# S_NES2USB.net
KiCad netlist of a schematic drawn in EAGLE
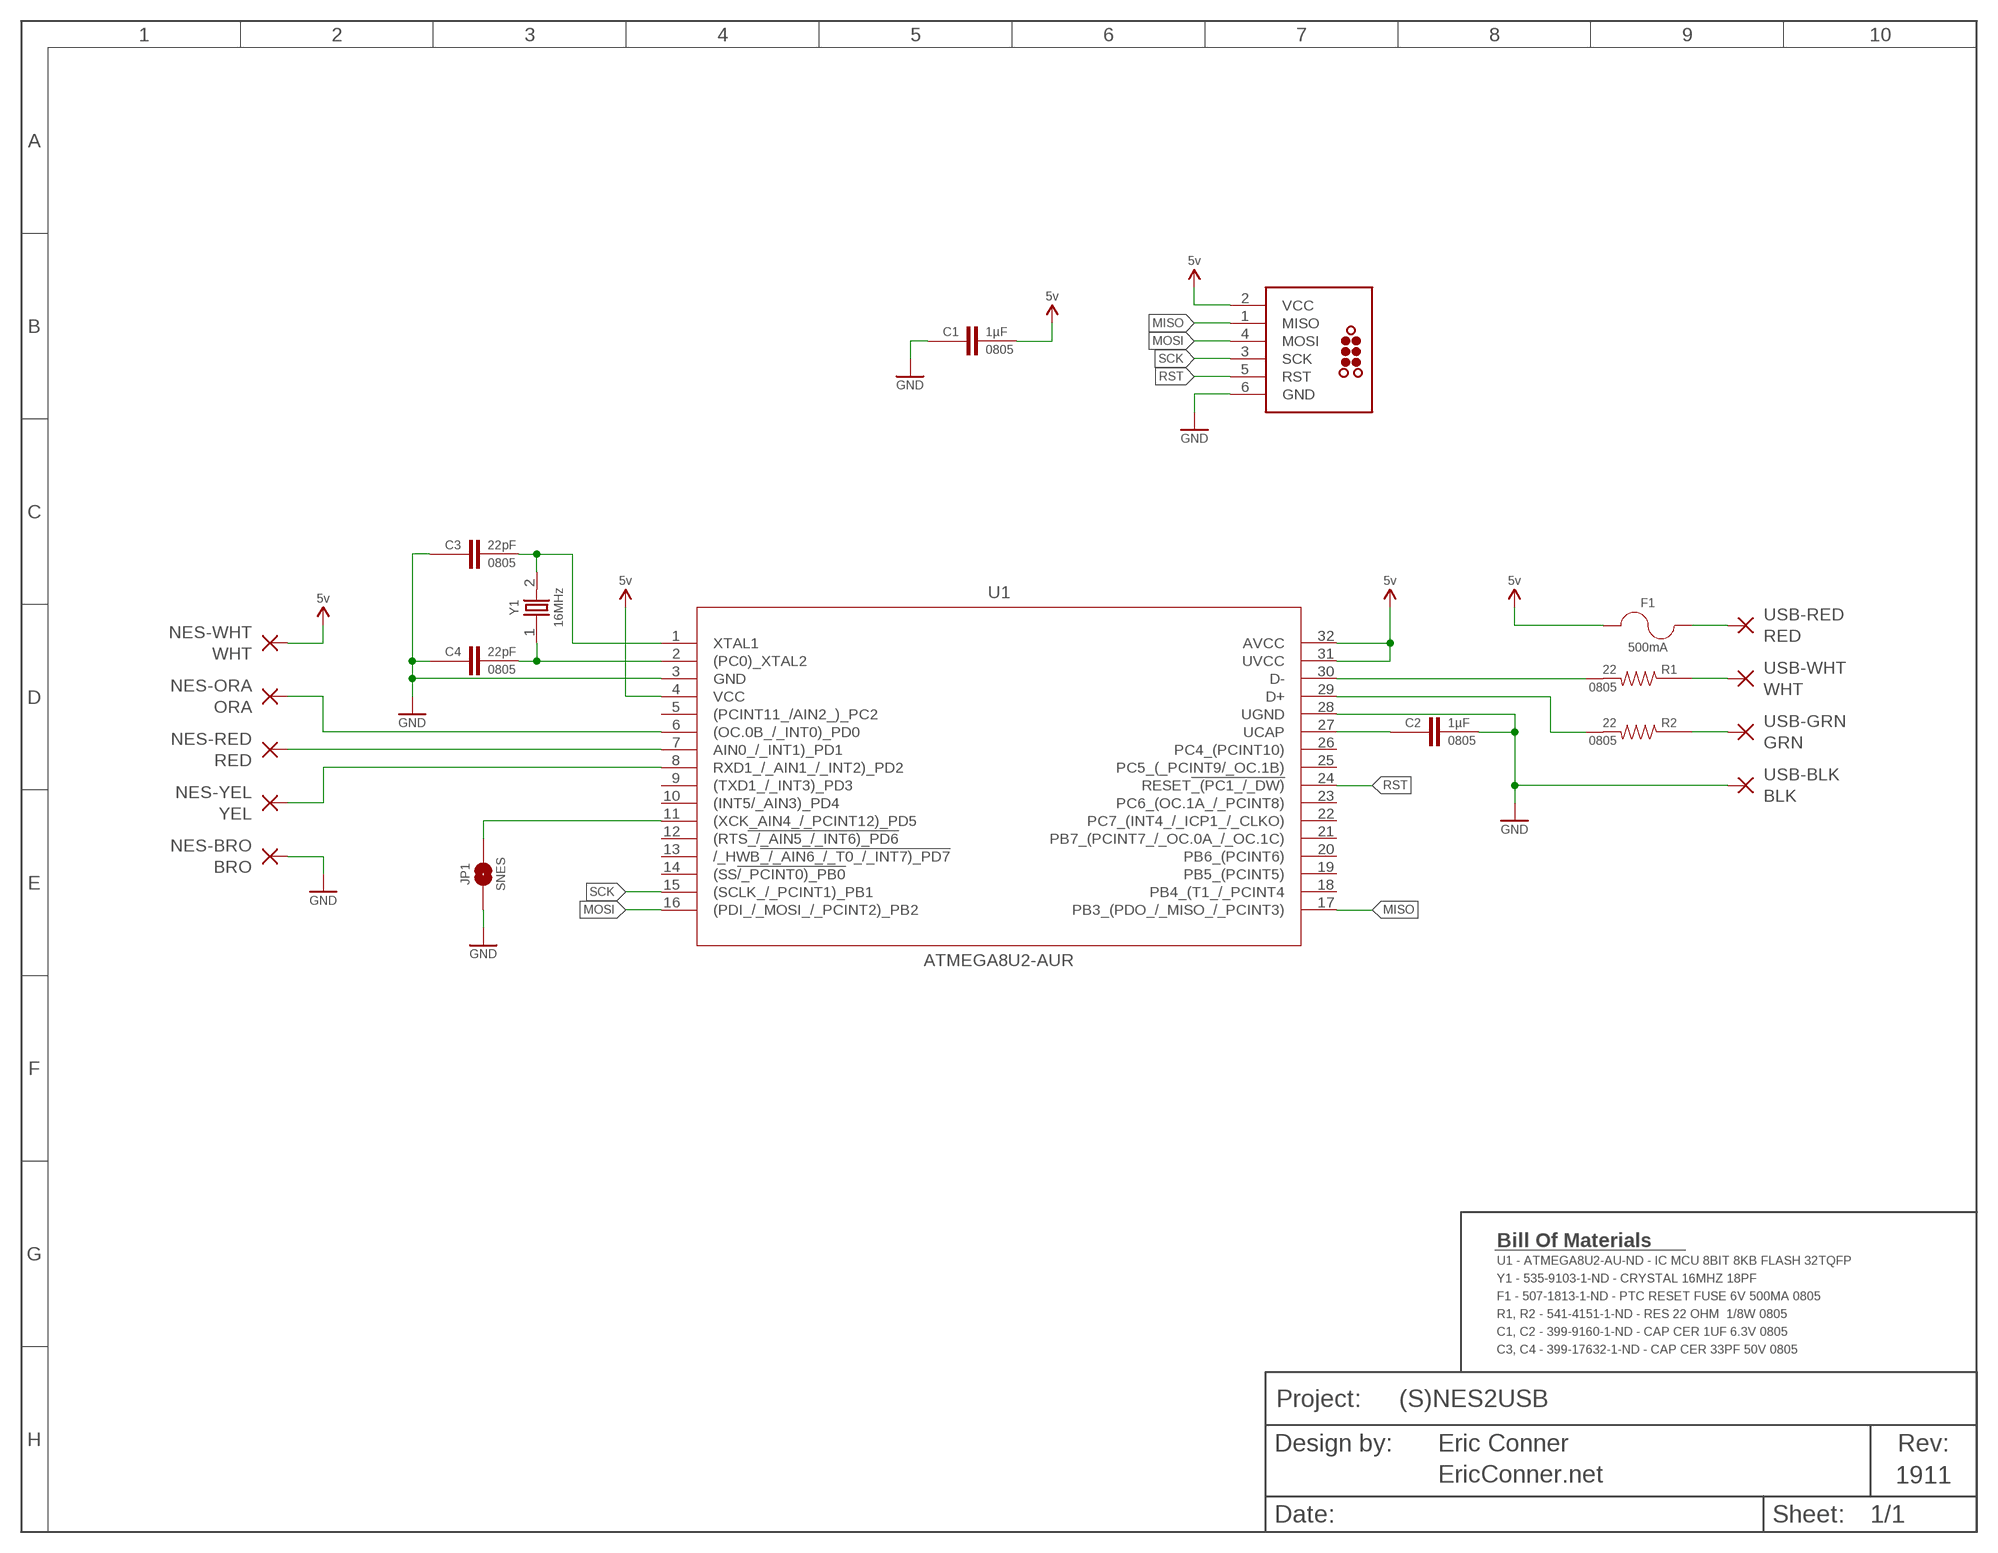
[diagram p0: schematic, sheet 1]

(export (version "E")
  (design (tool "Eeschema 10.0.6"))
  (components
    (comp (ref "BORDER1")
      (value "BORDER_LETTER-MINIMAL")
      (footprint "eagle-import:MINIMAL_LOGO")
      (fields
        (field (name "DESIGNER") "Eric Conner")
        (field (name "PROJECT") "(S)NES2USB")
        (field (name "VERSION") "1911")
        (field (name "WEBSITE") "EricConner.net")
        (field (name "DESIGNER_1") "Eric Conner")
        (field (name "PROJECT_1") "(S)NES2USB")
        (field (name "VERSION_1") "1911")
        (field (name "WEBSITE_1") "EricConner.net")
      )
      (libsource (lib "eagle-import") (part "BORDER_LETTER-MINIMAL"))
    )
    (comp (ref "C1")
      (value "1µF")
      (footprint "eagle-import:0805")
      (fields (field (name "ATTRIBUTE") "0805"))
      (libsource (lib "eagle-import") (part "CAP-0805"))
    )
    (comp (ref "C2")
      (value "1µF")
      (footprint "eagle-import:0805")
      (fields (field (name "ATTRIBUTE") "0805"))
      (libsource (lib "eagle-import") (part "CAP-0805"))
    )
    (comp (ref "C3")
      (value "22pF")
      (footprint "eagle-import:0805")
      (fields (field (name "ATTRIBUTE") "0805"))
      (libsource (lib "eagle-import") (part "CAP-0805"))
    )
    (comp (ref "C4")
      (value "22pF")
      (footprint "eagle-import:0805")
      (fields (field (name "ATTRIBUTE") "0805"))
      (libsource (lib "eagle-import") (part "CAP-0805"))
    )
    (comp (ref "F1")
      (value "500mA")
      (footprint "eagle-import:0805")
      (libsource (lib "eagle-import") (part "POLYFUSE0ZCK0050FF2E"))
    )
    (comp (ref "J1")
      (value "TC2030")
      (footprint "eagle-import:TC2030")
      (libsource (lib "eagle-import") (part "TC2030"))
    )
    (comp (ref "JP1")
      (value "SNES")
      (footprint "eagle-import:SMT-JUMPER_2_NO_SILK")
      (libsource (lib "eagle-import") (part "JUMPER-SMT_2_NO_SILK"))
    )
    (comp (ref "NES-BRO")
      (value "BRO")
      (footprint "eagle-import:SMD1,27-2,54")
      (libsource (lib "eagle-import") (part "WIREPADSMD1,27-254"))
    )
    (comp (ref "NES-ORA")
      (value "ORA")
      (footprint "eagle-import:SMD1,27-2,54")
      (libsource (lib "eagle-import") (part "WIREPADSMD1,27-254"))
    )
    (comp (ref "NES-RED")
      (value "RED")
      (footprint "eagle-import:SMD1,27-2,54")
      (libsource (lib "eagle-import") (part "WIREPADSMD1,27-254"))
    )
    (comp (ref "NES-WHT")
      (value "WHT")
      (footprint "eagle-import:SMD1,27-2,54")
      (libsource (lib "eagle-import") (part "WIREPADSMD1,27-254"))
    )
    (comp (ref "NES-YEL")
      (value "YEL")
      (footprint "eagle-import:SMD1,27-2,54")
      (libsource (lib "eagle-import") (part "WIREPADSMD1,27-254"))
    )
    (comp (ref "R1")
      (value "22")
      (footprint "eagle-import:0805")
      (fields (field (name "ATTRIBUTE") "0805"))
      (libsource (lib "eagle-import") (part "RESISTOR-0805"))
    )
    (comp (ref "R2")
      (value "22")
      (footprint "eagle-import:0805")
      (fields (field (name "ATTRIBUTE") "0805"))
      (libsource (lib "eagle-import") (part "RESISTOR-0805"))
    )
    (comp (ref "U1")
      (value "ATMEGA8U2-AUR")
      (footprint "eagle-import:TQFP32")
      (fields (field (name "MANUFACTURER_PART_NUMBER") "ATMEGA8U2AUR"))
      (libsource (lib "eagle-import") (part "ATMEGA8U2-AUR"))
    )
    (comp (ref "USB-BLK")
      (value "BLK")
      (footprint "eagle-import:SMD1,27-2,54")
      (libsource (lib "eagle-import") (part "WIREPADSMD1,27-254"))
    )
    (comp (ref "USB-GRN")
      (value "GRN")
      (footprint "eagle-import:SMD1,27-2,54")
      (libsource (lib "eagle-import") (part "WIREPADSMD1,27-254"))
    )
    (comp (ref "USB-RED")
      (value "RED")
      (footprint "eagle-import:SMD1,27-2,54")
      (libsource (lib "eagle-import") (part "WIREPADSMD1,27-254"))
    )
    (comp (ref "USB-WHT")
      (value "WHT")
      (footprint "eagle-import:SMD1,27-2,54")
      (libsource (lib "eagle-import") (part "WIREPADSMD1,27-254"))
    )
    (comp (ref "Y1")
      (value "16MHz")
      (footprint "eagle-import:XTAL500X320X130N")
      (fields
        (field (name "DIGI-KEY_PART_NUMBER") "535-9103-1-ND")
        (field (name "MF") "Abracon")
        (field (name "MP") "ABM3-16.000MHZ-B2-T")
      )
      (libsource (lib "eagle-import") (part "ABM3-16.000MHZ-B2-T"))
    )
  )
  (nets
    (net (code "1") (name "5V") (class "Default")
      (node (ref "C1") (pin "2") (pinfunction "2_2") (pintype "passive"))
      (node (ref "F1") (pin "2") (pinfunction "2_2") (pintype "bidirectional"))
      (node (ref "J1") (pin "2") (pinfunction "VCC_2") (pintype "power_in"))
      (node (ref "NES-WHT") (pin "1") (pinfunction "P_1") (pintype "passive"))
      (node (ref "U1") (pin "31") (pinfunction "UVCC_31") (pintype "power_in"))
      (node (ref "U1") (pin "32") (pinfunction "AVCC_32") (pintype "power_in"))
      (node (ref "U1") (pin "4") (pinfunction "VCC_4") (pintype "power_in"))
    )
    (net (code "2") (name "GND") (class "Default")
      (node (ref "C1") (pin "1") (pinfunction "1_1") (pintype "passive"))
      (node (ref "C2") (pin "2") (pinfunction "2_2") (pintype "passive"))
      (node (ref "C3") (pin "1") (pinfunction "1_1") (pintype "passive"))
      (node (ref "C4") (pin "1") (pinfunction "1_1") (pintype "passive"))
      (node (ref "J1") (pin "6") (pinfunction "GND_6") (pintype "power_in"))
      (node (ref "JP1") (pin "1") (pinfunction "1_1") (pintype "passive"))
      (node (ref "NES-BRO") (pin "1") (pinfunction "P_1") (pintype "passive"))
      (node (ref "U1") (pin "28") (pinfunction "UGND_28") (pintype "power_in"))
      (node (ref "U1") (pin "3") (pinfunction "GND_3") (pintype "power_in"))
      (node (ref "USB-BLK") (pin "1") (pinfunction "P_1") (pintype "passive"))
    )
    (net (code "3") (name "MISO") (class "Default")
      (node (ref "J1") (pin "1") (pinfunction "MISO_1") (pintype "bidirectional"))
      (node (ref "U1") (pin "17") (pinfunction "PB3_(PDO_/_MISO_/_PCINT3)_17") (pintype "bidirectional"))
    )
    (net (code "4") (name "MOSI") (class "Default")
      (node (ref "J1") (pin "4") (pinfunction "MOSI_4") (pintype "bidirectional"))
      (node (ref "U1") (pin "16") (pinfunction "(PDI_/_MOSI_/_PCINT2)_PB2_16") (pintype "bidirectional"))
    )
    (net (code "5") (name "Net-(NES-ORA-P)") (class "Default")
      (node (ref "NES-ORA") (pin "1") (pinfunction "P_1") (pintype "passive"))
      (node (ref "U1") (pin "6") (pinfunction "(OC.0B_/_INT0)_PD0_6") (pintype "bidirectional"))
    )
    (net (code "6") (name "Net-(NES-RED-P)") (class "Default")
      (node (ref "NES-RED") (pin "1") (pinfunction "P_1") (pintype "passive"))
      (node (ref "U1") (pin "7") (pinfunction "AIN0_/_INT1)_PD1_7") (pintype "bidirectional"))
    )
    (net (code "7") (name "Net-(NES-YEL-P)") (class "Default")
      (node (ref "NES-YEL") (pin "1") (pinfunction "P_1") (pintype "passive"))
      (node (ref "U1") (pin "8") (pinfunction "RXD1_/_AIN1_/_INT2)_PD2_8") (pintype "bidirectional"))
    )
    (net (code "8") (name "Net-(U1-(PC0)_XTAL2)") (class "Default")
      (node (ref "C4") (pin "2") (pinfunction "2_2") (pintype "passive"))
      (node (ref "U1") (pin "2") (pinfunction "(PC0)_XTAL2_2") (pintype "bidirectional"))
      (node (ref "Y1") (pin "1") (pinfunction "1_1") (pintype "passive"))
    )
    (net (code "9") (name "Net-(U1-(XCK_AIN4_{slash}_PCINT12)_PD5)") (class "Default")
      (node (ref "JP1") (pin "2") (pinfunction "2_2") (pintype "passive"))
      (node (ref "U1") (pin "11") (pinfunction "(XCK_AIN4_/_PCINT12)_PD5_11") (pintype "bidirectional"))
    )
    (net (code "10") (name "Net-(U1-D+)") (class "Default")
      (node (ref "R2") (pin "2") (pinfunction "2_2") (pintype "passive"))
      (node (ref "U1") (pin "29") (pinfunction "D+_29") (pintype "passive"))
    )
    (net (code "11") (name "Net-(U1-D-)") (class "Default")
      (node (ref "R1") (pin "2") (pinfunction "2_2") (pintype "passive"))
      (node (ref "U1") (pin "30") (pinfunction "D-_30") (pintype "passive"))
    )
    (net (code "12") (name "Net-(U1-UCAP)") (class "Default")
      (node (ref "C2") (pin "1") (pinfunction "1_1") (pintype "passive"))
      (node (ref "U1") (pin "27") (pinfunction "UCAP_27") (pintype "power_in"))
    )
    (net (code "13") (name "Net-(U1-XTAL1)") (class "Default")
      (node (ref "C3") (pin "2") (pinfunction "2_2") (pintype "passive"))
      (node (ref "U1") (pin "1") (pinfunction "XTAL1_1") (pintype "input"))
      (node (ref "Y1") (pin "2") (pinfunction "2_2") (pintype "passive"))
    )
    (net (code "14") (name "Net-(USB-GRN-P)") (class "Default")
      (node (ref "R2") (pin "1") (pinfunction "1_1") (pintype "passive"))
      (node (ref "USB-GRN") (pin "1") (pinfunction "P_1") (pintype "passive"))
    )
    (net (code "15") (name "Net-(USB-RED-P)") (class "Default")
      (node (ref "F1") (pin "1") (pinfunction "1_1") (pintype "bidirectional"))
      (node (ref "USB-RED") (pin "1") (pinfunction "P_1") (pintype "passive"))
    )
    (net (code "16") (name "Net-(USB-WHT-P)") (class "Default")
      (node (ref "R1") (pin "1") (pinfunction "1_1") (pintype "passive"))
      (node (ref "USB-WHT") (pin "1") (pinfunction "P_1") (pintype "passive"))
    )
    (net (code "17") (name "RST") (class "Default")
      (node (ref "J1") (pin "5") (pinfunction "RST_5") (pintype "bidirectional"))
      (node (ref "U1") (pin "24") (pinfunction "RESET~{_(PC1_/_DW})_24") (pintype "bidirectional"))
    )
    (net (code "18") (name "SCK") (class "Default")
      (node (ref "J1") (pin "3") (pinfunction "SCK_3") (pintype "bidirectional"))
      (node (ref "U1") (pin "15") (pinfunction "(SCLK_/_PCINT1)_PB1_15") (pintype "bidirectional"))
    )
    (net (code "19") (name "unconnected-(U1-(INT5{slash}_AIN3)_PD4-Pad10)") (class "Default")
      (node (ref "U1") (pin "10") (pinfunction "(INT5/_AIN3)_PD4_10") (pintype "bidirectional"))
    )
    (net (code "20") (name "unconnected-(U1-(PCINT11_{slash}AIN2_)_PC2-Pad5)") (class "Default")
      (node (ref "U1") (pin "5") (pinfunction "(PCINT11_/AIN2_)_PC2_5") (pintype "bidirectional"))
    )
    (net (code "21") (name "unconnected-(U1-(RTS~{_{slash}_AIN5_{slash}_INT6})_PD6-Pad12)") (class "Default")
      (node (ref "U1") (pin "12") (pinfunction "(RTS~{_/_AIN5_/_INT6})_PD6_12") (pintype "bidirectional"))
    )
    (net (code "22") (name "unconnected-(U1-(SS~{{slash}_PCINT0})_PB0-Pad14)") (class "Default")
      (node (ref "U1") (pin "14") (pinfunction "(SS~{/_PCINT0})_PB0_14") (pintype "bidirectional"))
    )
    (net (code "23") (name "unconnected-(U1-(TXD1_{slash}_INT3)_PD3-Pad9)") (class "Default")
      (node (ref "U1") (pin "9") (pinfunction "(TXD1_/_INT3)_PD3_9") (pintype "bidirectional"))
    )
    (net (code "24") (name "unconnected-(U1-PB4_(T1_{slash}_PCINT4-Pad18)") (class "Default")
      (node (ref "U1") (pin "18") (pinfunction "PB4_(T1_/_PCINT4_18") (pintype "bidirectional"))
    )
    (net (code "25") (name "unconnected-(U1-PB5_(PCINT5)-Pad19)") (class "Default")
      (node (ref "U1") (pin "19") (pinfunction "PB5_(PCINT5)_19") (pintype "bidirectional"))
    )
    (net (code "26") (name "unconnected-(U1-PB6_(PCINT6)-Pad20)") (class "Default")
      (node (ref "U1") (pin "20") (pinfunction "PB6_(PCINT6)_20") (pintype "bidirectional"))
    )
    (net (code "27") (name "unconnected-(U1-PB7_(PCINT7_{slash}_OC.0A_{slash}_OC.1C)-Pad21)") (class "Default")
      (node (ref "U1") (pin "21") (pinfunction "PB7_(PCINT7_/_OC.0A_/_OC.1C)_21") (pintype "bidirectional"))
    )
    (net (code "28") (name "unconnected-(U1-PC4_(PCINT10)-Pad26)") (class "Default")
      (node (ref "U1") (pin "26") (pinfunction "PC4_(PCINT10)_26") (pintype "bidirectional"))
    )
    (net (code "29") (name "unconnected-(U1-PC5_(_PCINT9{slash}_OC.1B)-Pad25)") (class "Default")
      (node (ref "U1") (pin "25") (pinfunction "PC5_(_PCINT9/_OC.1B)_25") (pintype "bidirectional"))
    )
    (net (code "30") (name "unconnected-(U1-PC6_(OC.1A_{slash}_PCINT8)-Pad23)") (class "Default")
      (node (ref "U1") (pin "23") (pinfunction "PC6_(OC.1A_/_PCINT8)_23") (pintype "bidirectional"))
    )
    (net (code "31") (name "unconnected-(U1-PC7_(INT4_{slash}_ICP1_{slash}_CLKO)-Pad22)") (class "Default")
      (node (ref "U1") (pin "22") (pinfunction "PC7_(INT4_/_ICP1_/_CLKO)_22") (pintype "bidirectional"))
    )
    (net (code "32") (name "unconnected-(U1-{slash}_HWB~{_{slash}_AIN6_{slash}_T0_{slash}_INT7})_PD7-Pad13)") (class "Default")
      (node (ref "U1") (pin "13") (pinfunction "/_HWB~{_/_AIN6_/_T0_/_INT7})_PD7_13") (pintype "bidirectional"))
    )
  )
)
